# rpi-management.net
KiCad netlist of a schematic drawn in EAGLE
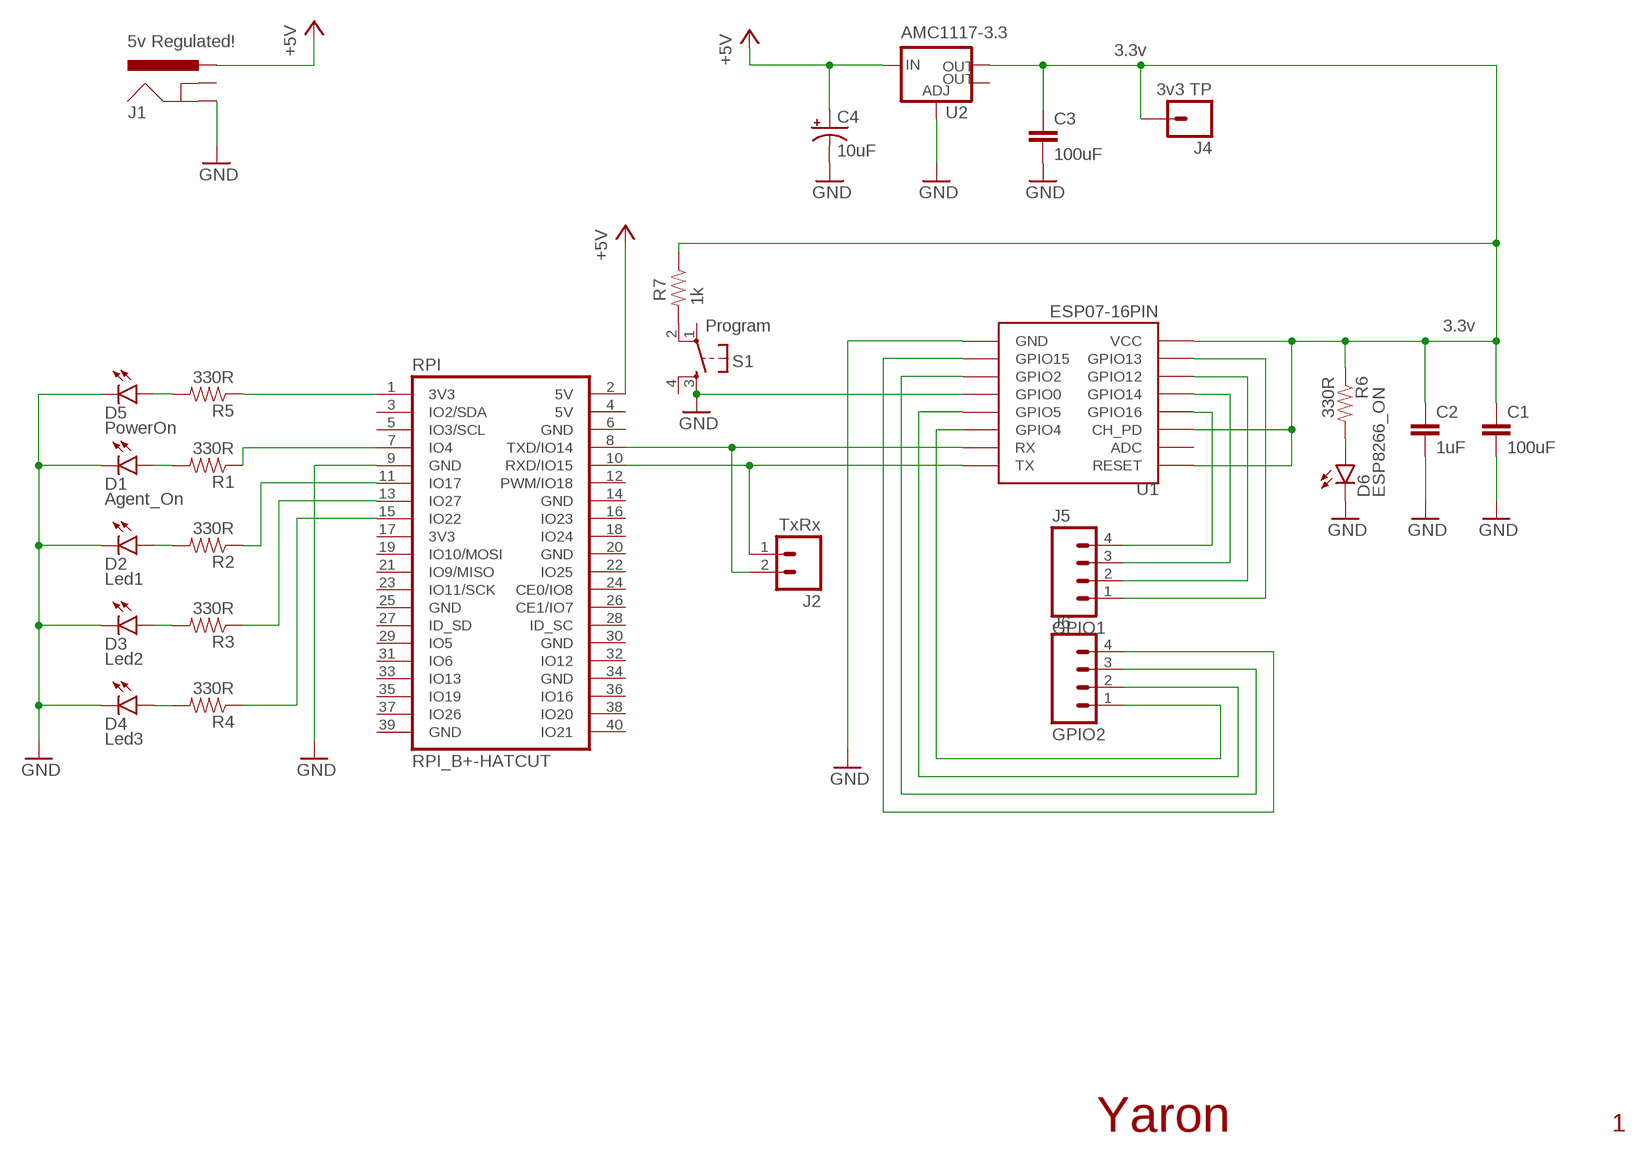
[diagram p0: schematic, sheet 1]

(export (version "E")
  (design (tool "Eeschema 10.0.6"))
  (components
    (comp (ref "C1")
      (value "100uF")
      (footprint "eagle-import:0603-CAP")
      (libsource (lib "eagle-import") (part "CAP0603-CAP"))
    )
    (comp (ref "C2")
      (value "1uF")
      (footprint "eagle-import:0603-CAP")
      (libsource (lib "eagle-import") (part "CAP0603-CAP"))
    )
    (comp (ref "C3")
      (value "100uF")
      (footprint "eagle-import:0603-CAP")
      (libsource (lib "eagle-import") (part "CAP0603-CAP"))
    )
    (comp (ref "C4")
      (value "10uF")
      (footprint "eagle-import:EIA6032")
      (libsource (lib "eagle-import") (part "CAP_POL6032"))
    )
    (comp (ref "D1")
      (value "Agent_On")
      (footprint "eagle-import:LED-0603")
      (libsource (lib "eagle-import") (part "LED0603"))
    )
    (comp (ref "D2")
      (value "Led1")
      (footprint "eagle-import:LED-0603")
      (libsource (lib "eagle-import") (part "LED0603"))
    )
    (comp (ref "D3")
      (value "Led2")
      (footprint "eagle-import:LED-0603")
      (libsource (lib "eagle-import") (part "LED0603"))
    )
    (comp (ref "D4")
      (value "Led3")
      (footprint "eagle-import:LED-0603")
      (libsource (lib "eagle-import") (part "LED0603"))
    )
    (comp (ref "D5")
      (value "PowerOn")
      (footprint "eagle-import:LED-0603")
      (libsource (lib "eagle-import") (part "LED0603"))
    )
    (comp (ref "D6")
      (value "ESP8266_ON")
      (footprint "eagle-import:LED-0603")
      (libsource (lib "eagle-import") (part "LED0603"))
    )
    (comp (ref "J1")
      (value "5v Regulated!")
      (footprint "eagle-import:POWER_JACK_SLOT")
      (libsource (lib "eagle-import") (part "POWER_JACKSLT"))
    )
    (comp (ref "J2")
      (value "TxRx")
      (footprint "eagle-import:1X02")
      (libsource (lib "eagle-import") (part "M02PTH"))
    )
    (comp (ref "J4")
      (value "3v3 TP")
      (footprint "eagle-import:1X01")
      (libsource (lib "eagle-import") (part "M01PTH"))
    )
    (comp (ref "J5")
      (value "GPIO1")
      (footprint "eagle-import:1X04")
      (libsource (lib "eagle-import") (part "M04PTH"))
    )
    (comp (ref "J6")
      (value "GPIO2")
      (footprint "eagle-import:1X04")
      (libsource (lib "eagle-import") (part "M04PTH"))
    )
    (comp (ref "R1")
      (value "330R")
      (footprint "eagle-import:0603-RES")
      (libsource (lib "eagle-import") (part "RESISTOR0603-RES"))
    )
    (comp (ref "R2")
      (value "330R")
      (footprint "eagle-import:0603-RES")
      (libsource (lib "eagle-import") (part "RESISTOR0603-RES"))
    )
    (comp (ref "R3")
      (value "330R")
      (footprint "eagle-import:0603-RES")
      (libsource (lib "eagle-import") (part "RESISTOR0603-RES"))
    )
    (comp (ref "R4")
      (value "330R")
      (footprint "eagle-import:0603-RES")
      (libsource (lib "eagle-import") (part "RESISTOR0603-RES"))
    )
    (comp (ref "R5")
      (value "330R")
      (footprint "eagle-import:0603-RES")
      (libsource (lib "eagle-import") (part "RESISTOR0603-RES"))
    )
    (comp (ref "R6")
      (value "330R")
      (footprint "eagle-import:0603-RES")
      (libsource (lib "eagle-import") (part "RESISTOR0603-RES"))
    )
    (comp (ref "R7")
      (value "1k")
      (footprint "eagle-import:0603-RES")
      (libsource (lib "eagle-import") (part "RESISTOR0603-RES"))
    )
    (comp (ref "RPI")
      (value "RPI_B+-HATCUT")
      (footprint "eagle-import:RPI-B+HAT_CUTOUT")
      (libsource (lib "eagle-import") (part "RPI_B+-HATCUT"))
    )
    (comp (ref "S1")
      (value "Program")
      (footprint "eagle-import:TACTILE-PTH")
      (libsource (lib "eagle-import") (part "TAC_SWITCHPTH"))
    )
    (comp (ref "U1")
      (value "ESP07-16PIN")
      (footprint "eagle-import:ESP07-16PIN")
      (libsource (lib "eagle-import") (part "ESP07-16PIN"))
    )
    (comp (ref "U2")
      (value "AMC1117-3.3")
      (footprint "eagle-import:SOT223")
      (libsource (lib "eagle-import") (part "V_REG_LM1117SOT223"))
    )
  )
  (nets
    (net (code "1") (name "+5V") (class "Default")
      (node (ref "C4") (pin "P$1") (pinfunction "+_P$1") (pintype "passive"))
      (node (ref "J1") (pin "PWR") (pinfunction "PWR_PWR") (pintype "bidirectional"))
      (node (ref "RPI") (pin "2") (pinfunction "5V_2") (pintype "passive"))
      (node (ref "U2") (pin "3") (pinfunction "IN_3") (pintype "input"))
    )
    (net (code "2") (name "GND") (class "Default")
      (node (ref "C1") (pin "2") (pinfunction "2_2") (pintype "passive"))
      (node (ref "C2") (pin "2") (pinfunction "2_2") (pintype "passive"))
      (node (ref "C3") (pin "2") (pinfunction "2_2") (pintype "passive"))
      (node (ref "C4") (pin "P$2") (pinfunction "-_P$2") (pintype "passive"))
      (node (ref "D1") (pin "C") (pinfunction "C_C") (pintype "passive"))
      (node (ref "D2") (pin "C") (pinfunction "C_C") (pintype "passive"))
      (node (ref "D3") (pin "C") (pinfunction "C_C") (pintype "passive"))
      (node (ref "D4") (pin "C") (pinfunction "C_C") (pintype "passive"))
      (node (ref "D5") (pin "C") (pinfunction "C_C") (pintype "passive"))
      (node (ref "D6") (pin "C") (pinfunction "C_C") (pintype "passive"))
      (node (ref "J1") (pin "GND@2") (pinfunction "GND_GND@2") (pintype "bidirectional"))
      (node (ref "RPI") (pin "9") (pinfunction "GND_9") (pintype "passive"))
      (node (ref "S1") (pin "3") (pinfunction "3_3") (pintype "passive"))
      (node (ref "U1") (pin "GND") (pinfunction "GND_GND") (pintype "bidirectional"))
      (node (ref "U1") (pin "GPIO0") (pinfunction "GPIO0_GPIO0") (pintype "bidirectional"))
      (node (ref "U2") (pin "1") (pinfunction "ADJ_1") (pintype "input"))
    )
    (net (code "3") (name "Net-(D1-PadA)") (class "Default")
      (node (ref "D1") (pin "A") (pinfunction "A_A") (pintype "passive"))
      (node (ref "R1") (pin "2") (pinfunction "2_2") (pintype "passive"))
    )
    (net (code "4") (name "Net-(D2-PadA)") (class "Default")
      (node (ref "D2") (pin "A") (pinfunction "A_A") (pintype "passive"))
      (node (ref "R2") (pin "2") (pinfunction "2_2") (pintype "passive"))
    )
    (net (code "5") (name "Net-(D3-PadA)") (class "Default")
      (node (ref "D3") (pin "A") (pinfunction "A_A") (pintype "passive"))
      (node (ref "R3") (pin "2") (pinfunction "2_2") (pintype "passive"))
    )
    (net (code "6") (name "Net-(D4-PadA)") (class "Default")
      (node (ref "D4") (pin "A") (pinfunction "A_A") (pintype "passive"))
      (node (ref "R4") (pin "2") (pinfunction "2_2") (pintype "passive"))
    )
    (net (code "7") (name "Net-(D5-PadA)") (class "Default")
      (node (ref "D5") (pin "A") (pinfunction "A_A") (pintype "passive"))
      (node (ref "R5") (pin "2") (pinfunction "2_2") (pintype "passive"))
    )
    (net (code "8") (name "Net-(D6-PadA)") (class "Default")
      (node (ref "D6") (pin "A") (pinfunction "A_A") (pintype "passive"))
      (node (ref "R6") (pin "2") (pinfunction "2_2") (pintype "passive"))
    )
    (net (code "9") (name "Net-(J5-Pad1)") (class "Default")
      (node (ref "J5") (pin "1") (pinfunction "1_1") (pintype "passive"))
      (node (ref "U1") (pin "GPIO13") (pinfunction "GPIO13_GPIO13") (pintype "bidirectional"))
    )
    (net (code "10") (name "Net-(J5-Pad2)") (class "Default")
      (node (ref "J5") (pin "2") (pinfunction "2_2") (pintype "passive"))
      (node (ref "U1") (pin "GPIO12") (pinfunction "GPIO12_GPIO12") (pintype "bidirectional"))
    )
    (net (code "11") (name "Net-(J5-Pad3)") (class "Default")
      (node (ref "J5") (pin "3") (pinfunction "3_3") (pintype "passive"))
      (node (ref "U1") (pin "GPIO14") (pinfunction "GPIO14_GPIO14") (pintype "bidirectional"))
    )
    (net (code "12") (name "Net-(J5-Pad4)") (class "Default")
      (node (ref "J5") (pin "4") (pinfunction "4_4") (pintype "passive"))
      (node (ref "U1") (pin "GPIO16") (pinfunction "GPIO16_GPIO16") (pintype "bidirectional"))
    )
    (net (code "13") (name "Net-(J6-Pad1)") (class "Default")
      (node (ref "J6") (pin "1") (pinfunction "1_1") (pintype "passive"))
      (node (ref "U1") (pin "GPIO4") (pinfunction "GPIO4_GPIO4") (pintype "bidirectional"))
    )
    (net (code "14") (name "Net-(J6-Pad2)") (class "Default")
      (node (ref "J6") (pin "2") (pinfunction "2_2") (pintype "passive"))
      (node (ref "U1") (pin "GPIO5") (pinfunction "GPIO5_GPIO5") (pintype "bidirectional"))
    )
    (net (code "15") (name "Net-(J6-Pad3)") (class "Default")
      (node (ref "J6") (pin "3") (pinfunction "3_3") (pintype "passive"))
      (node (ref "U1") (pin "GPIO2") (pinfunction "GPIO2_GPIO2") (pintype "bidirectional"))
    )
    (net (code "16") (name "Net-(J6-Pad4)") (class "Default")
      (node (ref "J6") (pin "4") (pinfunction "4_4") (pintype "passive"))
      (node (ref "U1") (pin "GPIO15") (pinfunction "GPIO15_GPIO15") (pintype "bidirectional"))
    )
    (net (code "17") (name "Net-(R5-Pad1)") (class "Default")
      (node (ref "R5") (pin "1") (pinfunction "1_1") (pintype "passive"))
      (node (ref "RPI") (pin "1") (pinfunction "3V3_1") (pintype "passive"))
    )
    (net (code "18") (name "Net-(R7-Pad2)") (class "Default")
      (node (ref "R7") (pin "2") (pinfunction "2_2") (pintype "passive"))
      (node (ref "S1") (pin "2") (pinfunction "2_2") (pintype "passive"))
    )
    (net (code "19") (name "Net-(RPI-IO4)") (class "Default")
      (node (ref "R1") (pin "1") (pinfunction "1_1") (pintype "passive"))
      (node (ref "RPI") (pin "7") (pinfunction "IO4_7") (pintype "passive"))
    )
    (net (code "20") (name "Net-(RPI-IO17)") (class "Default")
      (node (ref "R2") (pin "1") (pinfunction "1_1") (pintype "passive"))
      (node (ref "RPI") (pin "11") (pinfunction "IO17_11") (pintype "passive"))
    )
    (net (code "21") (name "Net-(RPI-IO22)") (class "Default")
      (node (ref "R4") (pin "1") (pinfunction "1_1") (pintype "passive"))
      (node (ref "RPI") (pin "15") (pinfunction "IO22_15") (pintype "passive"))
    )
    (net (code "22") (name "Net-(RPI-IO27)") (class "Default")
      (node (ref "R3") (pin "1") (pinfunction "1_1") (pintype "passive"))
      (node (ref "RPI") (pin "13") (pinfunction "IO27_13") (pintype "passive"))
    )
    (net (code "23") (name "Net-(RPI-RXD{slash}IO15)") (class "Default")
      (node (ref "J2") (pin "1") (pinfunction "1_1") (pintype "passive"))
      (node (ref "RPI") (pin "10") (pinfunction "RXD/IO15_10") (pintype "passive"))
      (node (ref "U1") (pin "TX") (pinfunction "TX_TX") (pintype "bidirectional"))
    )
    (net (code "24") (name "Net-(RPI-TXD{slash}IO14)") (class "Default")
      (node (ref "J2") (pin "2") (pinfunction "2_2") (pintype "passive"))
      (node (ref "RPI") (pin "8") (pinfunction "TXD/IO14_8") (pintype "passive"))
      (node (ref "U1") (pin "RX") (pinfunction "RX_RX") (pintype "bidirectional"))
    )
    (net (code "25") (name "Net-(U1-RESET)") (class "Default")
      (node (ref "C1") (pin "1") (pinfunction "1_1") (pintype "passive"))
      (node (ref "C2") (pin "1") (pinfunction "1_1") (pintype "passive"))
      (node (ref "C3") (pin "1") (pinfunction "1_1") (pintype "passive"))
      (node (ref "J4") (pin "1") (pinfunction "1_1") (pintype "passive"))
      (node (ref "R6") (pin "1") (pinfunction "1_1") (pintype "passive"))
      (node (ref "R7") (pin "1") (pinfunction "1_1") (pintype "passive"))
      (node (ref "U1") (pin "CH_PD") (pinfunction "CH_PD_CH_PD") (pintype "bidirectional"))
      (node (ref "U1") (pin "REST") (pinfunction "RESET_REST") (pintype "bidirectional"))
      (node (ref "U1") (pin "VCC") (pinfunction "VCC_VCC") (pintype "bidirectional"))
      (node (ref "U2") (pin "2") (pinfunction "OUT_2") (pintype "output"))
    )
    (net (code "26") (name "unconnected-(J1-GNDBREAK-PadGND@1)") (class "Default")
      (node (ref "J1") (pin "GND@1") (pinfunction "GNDBREAK_GND@1") (pintype "bidirectional"))
    )
    (net (code "27") (name "unconnected-(RPI-3V3-Pad17)") (class "Default")
      (node (ref "RPI") (pin "17") (pinfunction "3V3_17") (pintype "passive"))
    )
    (net (code "28") (name "unconnected-(RPI-5V-Pad4)") (class "Default")
      (node (ref "RPI") (pin "4") (pinfunction "5V_4") (pintype "passive"))
    )
    (net (code "29") (name "unconnected-(RPI-CE0{slash}IO8-Pad24)") (class "Default")
      (node (ref "RPI") (pin "24") (pinfunction "CE0/IO8_24") (pintype "passive"))
    )
    (net (code "30") (name "unconnected-(RPI-CE1{slash}IO7-Pad26)") (class "Default")
      (node (ref "RPI") (pin "26") (pinfunction "CE1/IO7_26") (pintype "passive"))
    )
    (net (code "31") (name "unconnected-(RPI-GND-Pad6)") (class "Default")
      (node (ref "RPI") (pin "6") (pinfunction "GND_6") (pintype "passive"))
    )
    (net (code "32") (name "unconnected-(RPI-GND-Pad14)") (class "Default")
      (node (ref "RPI") (pin "14") (pinfunction "GND_14") (pintype "passive"))
    )
    (net (code "33") (name "unconnected-(RPI-GND-Pad20)") (class "Default")
      (node (ref "RPI") (pin "20") (pinfunction "GND_20") (pintype "passive"))
    )
    (net (code "34") (name "unconnected-(RPI-GND-Pad25)") (class "Default")
      (node (ref "RPI") (pin "25") (pinfunction "GND_25") (pintype "passive"))
    )
    (net (code "35") (name "unconnected-(RPI-GND-Pad30)") (class "Default")
      (node (ref "RPI") (pin "30") (pinfunction "GND_30") (pintype "bidirectional"))
    )
    (net (code "36") (name "unconnected-(RPI-GND-Pad34)") (class "Default")
      (node (ref "RPI") (pin "34") (pinfunction "GND_34") (pintype "bidirectional"))
    )
    (net (code "37") (name "unconnected-(RPI-GND-Pad39)") (class "Default")
      (node (ref "RPI") (pin "39") (pinfunction "GND_39") (pintype "bidirectional"))
    )
    (net (code "38") (name "unconnected-(RPI-ID_SC-Pad28)") (class "Default")
      (node (ref "RPI") (pin "28") (pinfunction "ID_SC_28") (pintype "bidirectional"))
    )
    (net (code "39") (name "unconnected-(RPI-ID_SD-Pad27)") (class "Default")
      (node (ref "RPI") (pin "27") (pinfunction "ID_SD_27") (pintype "bidirectional"))
    )
    (net (code "40") (name "unconnected-(RPI-IO2{slash}SDA-Pad3)") (class "Default")
      (node (ref "RPI") (pin "3") (pinfunction "IO2/SDA_3") (pintype "passive"))
    )
    (net (code "41") (name "unconnected-(RPI-IO3{slash}SCL-Pad5)") (class "Default")
      (node (ref "RPI") (pin "5") (pinfunction "IO3/SCL_5") (pintype "passive"))
    )
    (net (code "42") (name "unconnected-(RPI-IO5-Pad29)") (class "Default")
      (node (ref "RPI") (pin "29") (pinfunction "IO5_29") (pintype "bidirectional"))
    )
    (net (code "43") (name "unconnected-(RPI-IO6-Pad31)") (class "Default")
      (node (ref "RPI") (pin "31") (pinfunction "IO6_31") (pintype "bidirectional"))
    )
    (net (code "44") (name "unconnected-(RPI-IO9{slash}MISO-Pad21)") (class "Default")
      (node (ref "RPI") (pin "21") (pinfunction "IO9/MISO_21") (pintype "passive"))
    )
    (net (code "45") (name "unconnected-(RPI-IO10{slash}MOSI-Pad19)") (class "Default")
      (node (ref "RPI") (pin "19") (pinfunction "IO10/MOSI_19") (pintype "passive"))
    )
    (net (code "46") (name "unconnected-(RPI-IO11{slash}SCK-Pad23)") (class "Default")
      (node (ref "RPI") (pin "23") (pinfunction "IO11/SCK_23") (pintype "passive"))
    )
    (net (code "47") (name "unconnected-(RPI-IO12-Pad32)") (class "Default")
      (node (ref "RPI") (pin "32") (pinfunction "IO12_32") (pintype "bidirectional"))
    )
    (net (code "48") (name "unconnected-(RPI-IO13-Pad33)") (class "Default")
      (node (ref "RPI") (pin "33") (pinfunction "IO13_33") (pintype "bidirectional"))
    )
    (net (code "49") (name "unconnected-(RPI-IO16-Pad36)") (class "Default")
      (node (ref "RPI") (pin "36") (pinfunction "IO16_36") (pintype "bidirectional"))
    )
    (net (code "50") (name "unconnected-(RPI-IO19-Pad35)") (class "Default")
      (node (ref "RPI") (pin "35") (pinfunction "IO19_35") (pintype "bidirectional"))
    )
    (net (code "51") (name "unconnected-(RPI-IO20-Pad38)") (class "Default")
      (node (ref "RPI") (pin "38") (pinfunction "IO20_38") (pintype "bidirectional"))
    )
    (net (code "52") (name "unconnected-(RPI-IO21-Pad40)") (class "Default")
      (node (ref "RPI") (pin "40") (pinfunction "IO21_40") (pintype "bidirectional"))
    )
    (net (code "53") (name "unconnected-(RPI-IO23-Pad16)") (class "Default")
      (node (ref "RPI") (pin "16") (pinfunction "IO23_16") (pintype "passive"))
    )
    (net (code "54") (name "unconnected-(RPI-IO24-Pad18)") (class "Default")
      (node (ref "RPI") (pin "18") (pinfunction "IO24_18") (pintype "passive"))
    )
    (net (code "55") (name "unconnected-(RPI-IO25-Pad22)") (class "Default")
      (node (ref "RPI") (pin "22") (pinfunction "IO25_22") (pintype "passive"))
    )
    (net (code "56") (name "unconnected-(RPI-IO26-Pad37)") (class "Default")
      (node (ref "RPI") (pin "37") (pinfunction "IO26_37") (pintype "bidirectional"))
    )
    (net (code "57") (name "unconnected-(RPI-PWM{slash}IO18-Pad12)") (class "Default")
      (node (ref "RPI") (pin "12") (pinfunction "PWM/IO18_12") (pintype "passive"))
    )
    (net (code "58") (name "unconnected-(S1-Pad1)") (class "Default")
      (node (ref "S1") (pin "1") (pinfunction "1_1") (pintype "passive"))
    )
    (net (code "59") (name "unconnected-(S1-Pad4)") (class "Default")
      (node (ref "S1") (pin "4") (pinfunction "4_4") (pintype "passive"))
    )
    (net (code "60") (name "unconnected-(U1-PadADC)") (class "Default")
      (node (ref "U1") (pin "ADC") (pinfunction "ADC_ADC") (pintype "bidirectional"))
    )
    (net (code "61") (name "unconnected-(U2-OUT-Pad4)") (class "Default")
      (node (ref "U2") (pin "4") (pinfunction "OUT_4") (pintype "output"))
    )
  )
)
